# SCH.net
KiCad netlist of a schematic drawn in Altium Designer
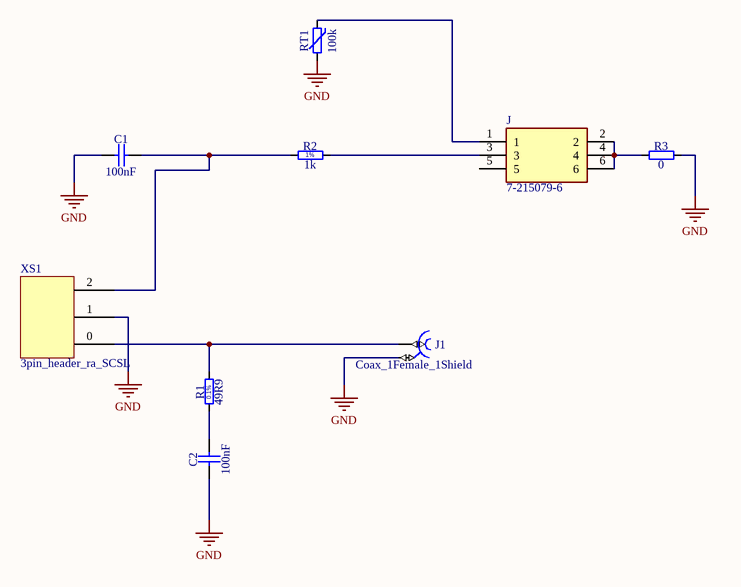
[diagram p0: SCH.SchDoc]

(export (version "E")
  (design (tool "Eeschema 10.0.6"))
  (components
    (comp (ref "C1")
      (value "100nF")
      (footprint "CAPC2012X135N")
      (description "Non-polarised capacitor")
      (fields
        (field (name "PART NUMBER") "CC0805_100NF_50V_10%_X7R")
        (field (name "VOLTAGE") "50V")
        (field (name "AUTHOR") "CERN DEM JLC")
      )
      (libsource (lib "Capacitors") (part "Capacitor - non polarized"))
    )
    (comp (ref "C2")
      (value "100nF")
      (footprint "CAPC2012X135N")
      (description "Non-polarised capacitor")
      (fields
        (field (name "PART NUMBER") "CC0805_100NF_50V_10%_X7R")
        (field (name "VOLTAGE") "50V")
        (field (name "AUTHOR") "CERN DEM JLC")
      )
      (libsource (lib "Capacitors") (part "Capacitor - non polarized"))
    )
    (comp (ref "J")
      (value "7-215079-6")
      (footprint "TE_7-215079-6")
      (description "Conn FFC Connector F 6 POS 1.27mm Solder ST Thru-Hole Automotive Box/Carton")
      (fields (field (name "MF") "TE Connectivity"))
      (libsource (lib "7-215079-6") (part "7-215079-6"))
    )
    (comp (ref "J1")
      (value "Coax_1Female_1Shield")
      (footprint "HUBER-SUHNER_85_MMCX-50-0-1/111_OE")
      (fields
        (field (name "PART NUMBER") "HUBER-SUHNER_85_MMCX-50-0-1/111_OE")
        (field (name "MANUFACTURER") "HUBER+SUHNER")
        (field (name "MANUFACTURER PART NUMBER") "85_MMCX-50-0-1/111_OE")
        (field (name "AUTHOR") "CERN DEM JLC")
      )
      (libsource (lib "Connectors") (part "Coax_1Female_1Shield"))
    )
    (comp (ref "R1")
      (value "49R9")
      (footprint "RESC2012X60N")
      (description "Resistor - 0.1%")
      (fields
        (field (name "PART NUMBER") "R0805_49R9_0.1%_0.1W_10PPM")
        (field (name "POWER") "0.1W")
        (field (name "AUTHOR") "CERN DEM JLC")
      )
      (libsource (lib "Resistors") (part "Resistor - 0.1%"))
    )
    (comp (ref "R2")
      (value "1k")
      (footprint "RESC2012X60N")
      (description "Resistor - 1%")
      (fields
        (field (name "PART NUMBER") "R0805_1K_1%_0.33W_100PPM_VISHAY_CRCW-HP")
        (field (name "POWER") "0.33W")
        (field (name "AUTHOR") "CERN DEM JLC")
      )
      (libsource (lib "Resistors") (part "Resistor - 1%"))
    )
    (comp (ref "R3")
      (value "0")
      (footprint "RESC2012X60N")
      (description "Resistor")
      (fields
        (field (name "PART NUMBER") "R0805_0R_JUMPER")
        (field (name "MANUFACTURER") "GENERIC")
        (field (name "AUTHOR") "CERN DEM JLC")
      )
      (libsource (lib "Resistors") (part "Resistor"))
    )
    (comp (ref "RT1")
      (value "100k")
      (footprint "THERMC2013X95N")
      (description "Thermistor NTC (Negative Temperature Coefficient)")
      (fields
        (field (name "PART NUMBER") "THERM_NTC_68K_VISHAY_NTCS0805E3683FXT")
        (field (name "POWER") "210mW")
        (field (name "AUTHOR") "CERN DEM JLC")
      )
      (libsource (lib "Resistors") (part "Thermistor NTC"))
    )
    (comp (ref "XS1")
      (value "3pin_header_ra_SCSL")
      (footprint "3pin_header_SCSL_FEMALE")
      (libsource (lib "Schlib") (part "3pin_header_ra_SCSL"))
    )
  )
  (nets
    (net (code "1") (name "GND") (class "Default")
      (node (ref "C1") (pin "1") (pinfunction "1_1") (pintype "passive"))
      (node (ref "C2") (pin "1") (pinfunction "1_1") (pintype "passive"))
      (node (ref "J1") (pin "2") (pinfunction "2_2") (pintype "bidirectional"))
      (node (ref "R3") (pin "2") (pinfunction "2_2") (pintype "passive"))
      (node (ref "RT1") (pin "1") (pinfunction "1_1") (pintype "passive"))
      (node (ref "XS1") (pin "1") (pinfunction "1_1") (pintype "passive"))
    )
    (net (code "2") (name "Net-(C1-Pad2)") (class "Default")
      (node (ref "C1") (pin "2") (pinfunction "2_2") (pintype "passive"))
      (node (ref "R2") (pin "1") (pinfunction "1_1") (pintype "passive"))
      (node (ref "XS1") (pin "2") (pinfunction "2_2") (pintype "passive"))
    )
    (net (code "3") (name "Net-(C2-Pad2)") (class "Default")
      (node (ref "C2") (pin "2") (pinfunction "2_2") (pintype "passive"))
      (node (ref "R1") (pin "1") (pinfunction "1_1") (pintype "passive"))
    )
    (net (code "4") (name "Net-(J-Pad1)") (class "Default")
      (node (ref "J") (pin "1") (pinfunction "1_1") (pintype "passive"))
      (node (ref "RT1") (pin "2") (pinfunction "2_2") (pintype "passive"))
    )
    (net (code "5") (name "Net-(J-Pad2)") (class "Default")
      (node (ref "J") (pin "2") (pinfunction "2_2") (pintype "passive"))
      (node (ref "J") (pin "4") (pinfunction "4_4") (pintype "passive"))
      (node (ref "J") (pin "6") (pinfunction "6_6") (pintype "passive"))
      (node (ref "R3") (pin "1") (pinfunction "1_1") (pintype "passive"))
    )
    (net (code "6") (name "Net-(J-Pad3)") (class "Default")
      (node (ref "J") (pin "3") (pinfunction "3_3") (pintype "passive"))
      (node (ref "R2") (pin "2") (pinfunction "2_2") (pintype "passive"))
    )
    (net (code "7") (name "Net-(J1-Pad1)") (class "Default")
      (node (ref "J1") (pin "1") (pinfunction "1_1") (pintype "bidirectional"))
      (node (ref "R1") (pin "2") (pinfunction "2_2") (pintype "passive"))
      (node (ref "XS1") (pin "0") (pinfunction "0_0") (pintype "passive"))
    )
    (net (code "8") (name "unconnected-(J-Pad5)") (class "Default")
      (node (ref "J") (pin "5") (pinfunction "5_5") (pintype "passive"))
    )
  )
)
